# EIS_Main_Interface.net
KiCad netlist of a schematic drawn in Altium Designer
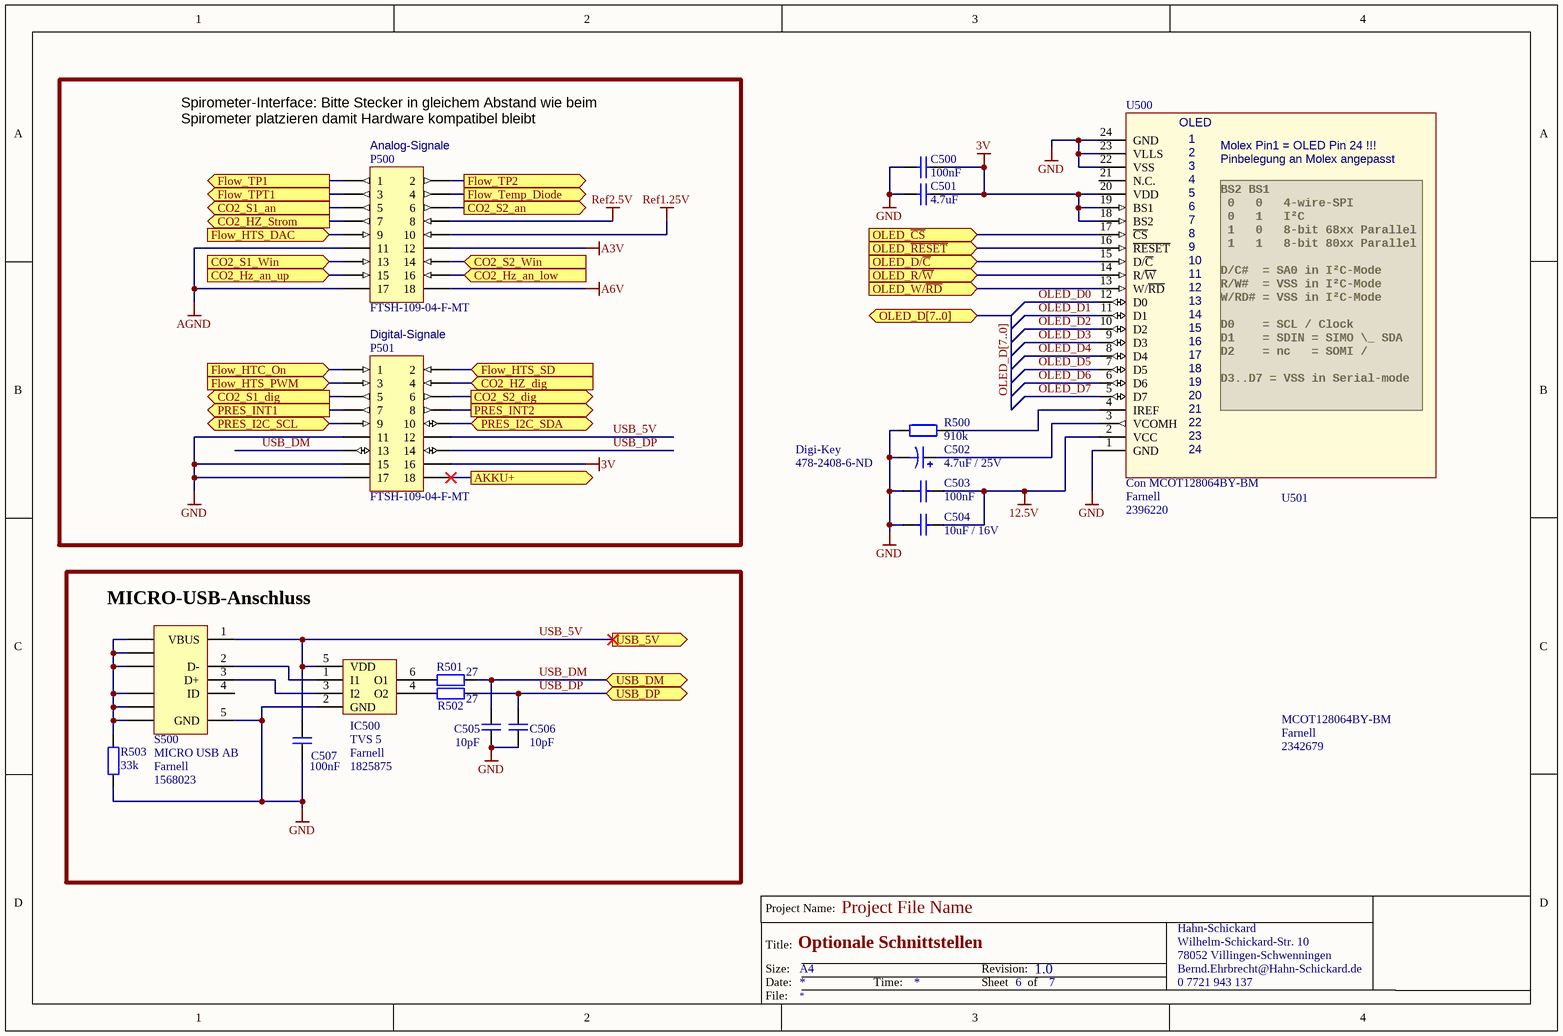
[diagram p0: EIS_Main_Interface.SchDoc]

(export (version "E")
  (design (tool "Eeschema 10.0.6"))
  (components
    (comp (ref "C500")
      (value "100nF")
      (footprint "CAPC1608N")
      (description "Ceramic Chip Capacitor - Standard")
      (fields (field (name "PUBLISHER") "Altium Limited"))
      (libsource (lib "KEMET Chip Capacitor") (part "C0805"))
    )
    (comp (ref "C501")
      (value "4.7uF")
      (footprint "CAPC2012N")
      (description "Ceramic Chip Capacitor - Standard")
      (fields (field (name "PUBLISHER") "Altium Limited"))
      (libsource (lib "KEMET Chip Capacitor") (part "C0805"))
    )
    (comp (ref "C502")
      (value "4.7uF / 25V")
      (footprint "C1210")
      (description "Polarized Capacitor (Surface Mount)")
      (fields
        (field (name "SUPPLIER 1") "Digi-Key")
        (field (name "SUPPLIER PART NUMBER 1") "478-2408-6-ND")
        (field (name "PUBLISHER") "Altium Limited")
      )
      (libsource (lib "Miscellaneous Devices") (part "Cap Pol3"))
    )
    (comp (ref "C503")
      (value "100nF")
      (footprint "CAPC1608N")
      (description "Ceramic Chip Capacitor - Standard")
      (fields (field (name "PUBLISHER") "Altium Limited"))
      (libsource (lib "KEMET Chip Capacitor") (part "C0805"))
    )
    (comp (ref "C504")
      (value "10uF / 16V")
      (footprint "CAPC2012N")
      (description "Ceramic Chip Capacitor - Standard")
      (fields (field (name "PUBLISHER") "Altium Limited"))
      (libsource (lib "KEMET Chip Capacitor") (part "C0805"))
    )
    (comp (ref "C505")
      (value "10pF")
      (footprint "CAPC1608N")
      (libsource (lib "My_Schlib_6_15") (part "Kondensator SMD Keramik"))
    )
    (comp (ref "C506")
      (value "10pF")
      (footprint "CAPC1608N")
      (libsource (lib "My_Schlib_6_15") (part "Kondensator SMD Keramik"))
    )
    (comp (ref "C507")
      (value "100nF")
      (footprint "CAPC1608N")
      (libsource (lib "My_Schlib_6_18") (part "Kondensator SMD Keramik"))
    )
    (comp (ref "IC500")
      (value "TVS 5")
      (footprint "SOT23-6")
      (fields (field (name "SUPPLIER 1") "Farnell") (field (name "SUPPLIER PART NUMBER 1") "1825875"))
      (libsource (lib "My_Schlib_6_15") (part "WE-TVS 2K 3,3V 23_6L"))
    )
    (comp (ref "P500")
      (value "FTSH-109-04-F-MT")
      (footprint "FTSH-109-01-X-MT-spezial")
      (description "Header, 9-Pin, Dual row")
      (fields (field (name "PUBLISHER") "Altium Limited"))
      (libsource (lib "Miscellaneous Connectors") (part "Header 9X2"))
    )
    (comp (ref "P501")
      (value "FTSH-109-04-F-MT")
      (footprint "FTSH-109-01-X-MT-spezial")
      (fields (field (name "PUBLISHER") "Altium Limited"))
      (libsource (lib "") (part "Header 9X2_1"))
    )
    (comp (ref "R500")
      (value "910k")
      (footprint "RESC1608N")
      (libsource (lib "My_Schlib_6_15") (part "Widerstand SMD"))
    )
    (comp (ref "R501")
      (value "27")
      (footprint "RESC1608N")
      (libsource (lib "My_Schlib_6_15") (part "Widerstand SMD"))
    )
    (comp (ref "R502")
      (value "27")
      (footprint "RESC1608N")
      (libsource (lib "My_Schlib_6_15") (part "Widerstand SMD"))
    )
    (comp (ref "R503")
      (value "33k")
      (footprint "RESC1608N")
      (libsource (lib "My_Schlib_6_18") (part "Widerstand SMD"))
    )
    (comp (ref "S500")
      (value "MICRO USB AB")
      (footprint "MICRO USB AB REC")
      (description "Micro USB AB, MOLEX-47589-0001, BOTTOM MOUNT")
      (fields (field (name "SUPPLIER 1") "Farnell") (field (name "SUPPLIER PART NUMBER 1") "1568023"))
      (libsource (lib "Mekka") (part "MICRO USB AB"))
    )
    (comp (ref "U500")
      (value "Con MCOT128064BY-BM")
      (footprint "Molex-52435-2471")
      (description "Connector für OLED, 128x64Pixel; 35x17mm / blau")
      (fields (field (name "SUPPLIER 1") "Farnell") (field (name "SUPPLIER PART NUMBER 1") "2396220"))
      (libsource (lib "MetaSensClampOn_BT") (part "Con MCOT128064BY-BM"))
    )
    (comp (ref "U501")
      (value "MCOT128064BY-BM")
      (description "OLED; blau; 128x64 Pixel;")
      (fields (field (name "SUPPLIER 1") "Farnell") (field (name "SUPPLIER PART NUMBER 1") "2342679"))
      (libsource (lib "MetaSensClampOn_BT") (part "MCOT128064BY-BM"))
    )
  )
  (nets
    (net (code "1") (name "/AKKU+") (class "Default")
      (node (ref "P501") (pin "18") (pinfunction "18_18") (pintype "power_in+no_connect"))
    )
    (net (code "2") (name "/CO2_HZ_Strom") (class "Default")
      (node (ref "P500") (pin "7") (pinfunction "7_7") (pintype "output"))
    )
    (net (code "3") (name "/CO2_HZ_dig") (class "Default")
      (node (ref "P501") (pin "4") (pinfunction "4_4") (pintype "input"))
    )
    (net (code "4") (name "/CO2_Hz_an_low") (class "Default")
      (node (ref "P500") (pin "16") (pinfunction "16_16") (pintype "input"))
    )
    (net (code "5") (name "/CO2_Hz_an_up") (class "Default")
      (node (ref "P500") (pin "15") (pinfunction "15_15") (pintype "input"))
    )
    (net (code "6") (name "/CO2_S1_Win") (class "Default")
      (node (ref "P500") (pin "13") (pinfunction "13_13") (pintype "input"))
    )
    (net (code "7") (name "/CO2_S1_an") (class "Default")
      (node (ref "P500") (pin "5") (pinfunction "5_5") (pintype "output"))
    )
    (net (code "8") (name "/CO2_S1_dig") (class "Default")
      (node (ref "P501") (pin "5") (pinfunction "5_5") (pintype "output"))
    )
    (net (code "9") (name "/CO2_S2_Win") (class "Default")
      (node (ref "P500") (pin "14") (pinfunction "14_14") (pintype "input"))
    )
    (net (code "10") (name "/CO2_S2_an") (class "Default")
      (node (ref "P500") (pin "6") (pinfunction "6_6") (pintype "output"))
    )
    (net (code "11") (name "/CO2_S2_dig") (class "Default")
      (node (ref "P501") (pin "6") (pinfunction "6_6") (pintype "output"))
    )
    (net (code "12") (name "/Flow_HTC_On") (class "Default")
      (node (ref "P501") (pin "1") (pinfunction "1_1") (pintype "input"))
    )
    (net (code "13") (name "/Flow_HTS_DAC") (class "Default")
      (node (ref "P500") (pin "9") (pinfunction "9_9") (pintype "input"))
    )
    (net (code "14") (name "/Flow_HTS_PWM") (class "Default")
      (node (ref "P501") (pin "3") (pinfunction "3_3") (pintype "input"))
    )
    (net (code "15") (name "/Flow_HTS_SD") (class "Default")
      (node (ref "P501") (pin "2") (pinfunction "2_2") (pintype "input"))
    )
    (net (code "16") (name "/Flow_TP1") (class "Default")
      (node (ref "P500") (pin "1") (pinfunction "1_1") (pintype "output"))
    )
    (net (code "17") (name "/Flow_TP2") (class "Default")
      (node (ref "P500") (pin "2") (pinfunction "2_2") (pintype "output"))
    )
    (net (code "18") (name "/Flow_TPT1") (class "Default")
      (node (ref "P500") (pin "3") (pinfunction "3_3") (pintype "output"))
    )
    (net (code "19") (name "/Flow_Temp_Diode") (class "Default")
      (node (ref "P500") (pin "4") (pinfunction "4_4") (pintype "output"))
    )
    (net (code "20") (name "/OLED_D0") (class "Default")
      (node (ref "U500") (pin "12") (pinfunction "D0_12") (pintype "bidirectional"))
    )
    (net (code "21") (name "/OLED_D1") (class "Default")
      (node (ref "U500") (pin "11") (pinfunction "D1_11") (pintype "bidirectional"))
    )
    (net (code "22") (name "/OLED_D2") (class "Default")
      (node (ref "U500") (pin "10") (pinfunction "D2_10") (pintype "bidirectional"))
    )
    (net (code "23") (name "/OLED_D3") (class "Default")
      (node (ref "U500") (pin "9") (pinfunction "D3_9") (pintype "bidirectional"))
    )
    (net (code "24") (name "/OLED_D4") (class "Default")
      (node (ref "U500") (pin "8") (pinfunction "D4_8") (pintype "bidirectional"))
    )
    (net (code "25") (name "/OLED_D5") (class "Default")
      (node (ref "U500") (pin "7") (pinfunction "D5_7") (pintype "bidirectional"))
    )
    (net (code "26") (name "/OLED_D6") (class "Default")
      (node (ref "U500") (pin "6") (pinfunction "D6_6") (pintype "bidirectional"))
    )
    (net (code "27") (name "/OLED_D7") (class "Default")
      (node (ref "U500") (pin "5") (pinfunction "D7_5") (pintype "bidirectional"))
    )
    (net (code "29") (name "/OLED_D{slash}~{C}") (class "Default")
      (node (ref "U500") (pin "15") (pinfunction "D/~{C}_15") (pintype "input"))
    )
    (net (code "30") (name "/OLED_R{slash}~{W}") (class "Default")
      (node (ref "U500") (pin "14") (pinfunction "R/~{W}_14") (pintype "input"))
    )
    (net (code "31") (name "/OLED_W{slash}~{RD}") (class "Default")
      (node (ref "U500") (pin "13") (pinfunction "W/~{RD}_13") (pintype "input"))
    )
    (net (code "32") (name "/OLED_~{CS}") (class "Default")
      (node (ref "U500") (pin "17") (pinfunction "~{CS}_17") (pintype "input"))
    )
    (net (code "33") (name "/OLED_~{RESET}") (class "Default")
      (node (ref "U500") (pin "16") (pinfunction "~{RESET}_16") (pintype "input"))
    )
    (net (code "34") (name "/PRES_I2C_SCL") (class "Default")
      (node (ref "P501") (pin "9") (pinfunction "9_9") (pintype "input"))
    )
    (net (code "35") (name "/PRES_I2C_SDA") (class "Default")
      (node (ref "P501") (pin "10") (pinfunction "10_10") (pintype "bidirectional"))
    )
    (net (code "36") (name "/PRES_INT1") (class "Default")
      (node (ref "P501") (pin "7") (pinfunction "7_7") (pintype "output"))
    )
    (net (code "37") (name "/PRES_INT2") (class "Default")
      (node (ref "P501") (pin "8") (pinfunction "8_8") (pintype "output"))
    )
    (net (code "38") (name "/USB_5V") (class "Default")
      (node (ref "C507") (pin "1") (pinfunction "1_1") (pintype "passive"))
      (node (ref "IC500") (pin "5") (pinfunction "VDD_5") (pintype "passive"))
      (node (ref "P501") (pin "12") (pinfunction "12_12") (pintype "power_in"))
      (node (ref "S500") (pin "1") (pinfunction "VBUS_1") (pintype "power_in"))
    )
    (net (code "39") (name "/USB_DM") (class "Default")
      (node (ref "C505") (pin "1") (pinfunction "1_1") (pintype "passive"))
      (node (ref "P501") (pin "13") (pinfunction "13_13") (pintype "bidirectional"))
      (node (ref "R501") (pin "2") (pinfunction "2_2") (pintype "passive"))
    )
    (net (code "40") (name "/USB_DP") (class "Default")
      (node (ref "C506") (pin "1") (pinfunction "1_1") (pintype "passive"))
      (node (ref "P501") (pin "14") (pinfunction "14_14") (pintype "bidirectional"))
      (node (ref "R502") (pin "2") (pinfunction "2_2") (pintype "passive"))
    )
    (net (code "41") (name "3V") (class "Default")
      (node (ref "C500") (pin "2") (pinfunction "2_2") (pintype "passive"))
      (node (ref "C501") (pin "2") (pinfunction "2_2") (pintype "passive"))
      (node (ref "P501") (pin "16") (pinfunction "16_16") (pintype "power_in"))
      (node (ref "U500") (pin "18") (pinfunction "BS2_18") (pintype "input"))
      (node (ref "U500") (pin "19") (pinfunction "BS1_19") (pintype "input"))
      (node (ref "U500") (pin "20") (pinfunction "VDD_20") (pintype "power_in"))
    )
    (net (code "42") (name "12.5V") (class "Default")
      (node (ref "C503") (pin "1") (pinfunction "1_1") (pintype "passive"))
      (node (ref "C504") (pin "1") (pinfunction "1_1") (pintype "passive"))
      (node (ref "U500") (pin "2") (pinfunction "VCC_2") (pintype "power_in"))
    )
    (net (code "43") (name "A3V") (class "Default")
      (node (ref "P500") (pin "12") (pinfunction "12_12") (pintype "power_in"))
    )
    (net (code "44") (name "A6V") (class "Default")
      (node (ref "P500") (pin "18") (pinfunction "18_18") (pintype "power_in"))
    )
    (net (code "45") (name "AGND") (class "Default")
      (node (ref "P500") (pin "11") (pinfunction "11_11") (pintype "power_in"))
      (node (ref "P500") (pin "17") (pinfunction "17_17") (pintype "power_in"))
    )
    (net (code "46") (name "GND") (class "Default")
      (node (ref "C500") (pin "1") (pinfunction "1_1") (pintype "passive"))
      (node (ref "C501") (pin "1") (pinfunction "1_1") (pintype "passive"))
      (node (ref "C502") (pin "2") (pinfunction "2_2") (pintype "passive"))
      (node (ref "C503") (pin "2") (pinfunction "2_2") (pintype "passive"))
      (node (ref "C504") (pin "2") (pinfunction "2_2") (pintype "passive"))
      (node (ref "C505") (pin "2") (pinfunction "2_2") (pintype "passive"))
      (node (ref "C506") (pin "2") (pinfunction "2_2") (pintype "passive"))
      (node (ref "C507") (pin "2") (pinfunction "2_2") (pintype "passive"))
      (node (ref "IC500") (pin "2") (pinfunction "GND_2") (pintype "passive"))
      (node (ref "P501") (pin "11") (pinfunction "11_11") (pintype "power_in"))
      (node (ref "P501") (pin "15") (pinfunction "15_15") (pintype "power_in"))
      (node (ref "P501") (pin "17") (pinfunction "17_17") (pintype "power_in"))
      (node (ref "R500") (pin "2") (pinfunction "2_2") (pintype "passive"))
      (node (ref "R503") (pin "1") (pinfunction "1_1") (pintype "passive"))
      (node (ref "S500") (pin "5") (pinfunction "GND_5") (pintype "power_in"))
      (node (ref "U500") (pin "1") (pinfunction "GND_1") (pintype "power_in"))
      (node (ref "U500") (pin "22") (pinfunction "VSS_22") (pintype "power_in"))
      (node (ref "U500") (pin "23") (pinfunction "VLLS_23") (pintype "power_in"))
      (node (ref "U500") (pin "24") (pinfunction "GND_24") (pintype "power_in"))
    )
    (net (code "47") (name "Net-(IC500-I1)") (class "Default")
      (node (ref "IC500") (pin "1") (pinfunction "I1_1") (pintype "passive"))
      (node (ref "S500") (pin "2") (pinfunction "D-_2") (pintype "passive"))
    )
    (net (code "48") (name "Net-(IC500-I2)") (class "Default")
      (node (ref "IC500") (pin "3") (pinfunction "I2_3") (pintype "passive"))
      (node (ref "S500") (pin "3") (pinfunction "D+_3") (pintype "passive"))
    )
    (net (code "49") (name "Net-(IC500-O1)") (class "Default")
      (node (ref "IC500") (pin "6") (pinfunction "O1_6") (pintype "passive"))
      (node (ref "R501") (pin "1") (pinfunction "1_1") (pintype "passive"))
    )
    (net (code "50") (name "Net-(IC500-O2)") (class "Default")
      (node (ref "IC500") (pin "4") (pinfunction "O2_4") (pintype "passive"))
      (node (ref "R502") (pin "1") (pinfunction "1_1") (pintype "passive"))
    )
    (net (code "51") (name "Net-(R503-Pad2)") (class "Default")
      (node (ref "R503") (pin "2") (pinfunction "2_2") (pintype "passive"))
      (node (ref "S500") (pin "GND1") (pinfunction "SHLD_GND1") (pintype "passive"))
      (node (ref "S500") (pin "GND2") (pinfunction "SHLD_GND2") (pintype "passive"))
      (node (ref "S500") (pin "GND3") (pinfunction "SHLD_GND3") (pintype "passive"))
      (node (ref "S500") (pin "GND4") (pinfunction "SHLD_GND4") (pintype "passive"))
      (node (ref "S500") (pin "GND5") (pinfunction "SHLD_GND5") (pintype "passive"))
      (node (ref "S500") (pin "GND6") (pinfunction "SHLD_GND6") (pintype "passive"))
    )
    (net (code "52") (name "Net-(U500-IREF)") (class "Default")
      (node (ref "R500") (pin "1") (pinfunction "1_1") (pintype "passive"))
      (node (ref "U500") (pin "4") (pinfunction "IREF_4") (pintype "passive"))
    )
    (net (code "53") (name "Net-(U500-VCOMH)") (class "Default")
      (node (ref "C502") (pin "1") (pinfunction "1_1") (pintype "passive"))
      (node (ref "U500") (pin "3") (pinfunction "VCOMH_3") (pintype "output"))
    )
    (net (code "54") (name "Ref1.25V") (class "Default")
      (node (ref "P500") (pin "10") (pinfunction "10_10") (pintype "input"))
    )
    (net (code "55") (name "Ref2.5V") (class "Default")
      (node (ref "P500") (pin "8") (pinfunction "8_8") (pintype "input"))
    )
    (net (code "56") (name "unconnected-(S500-ID-Pad4)") (class "Default")
      (node (ref "S500") (pin "4") (pinfunction "ID_4") (pintype "passive"))
    )
    (net (code "57") (name "unconnected-(U500-N.C.-Pad21)") (class "Default")
      (node (ref "U500") (pin "21") (pinfunction "N.C._21") (pintype "passive"))
    )
  )
)
